# SparkFun-Cherry-MX-Switch-Breakout.net
KiCad netlist of a schematic drawn in EAGLE
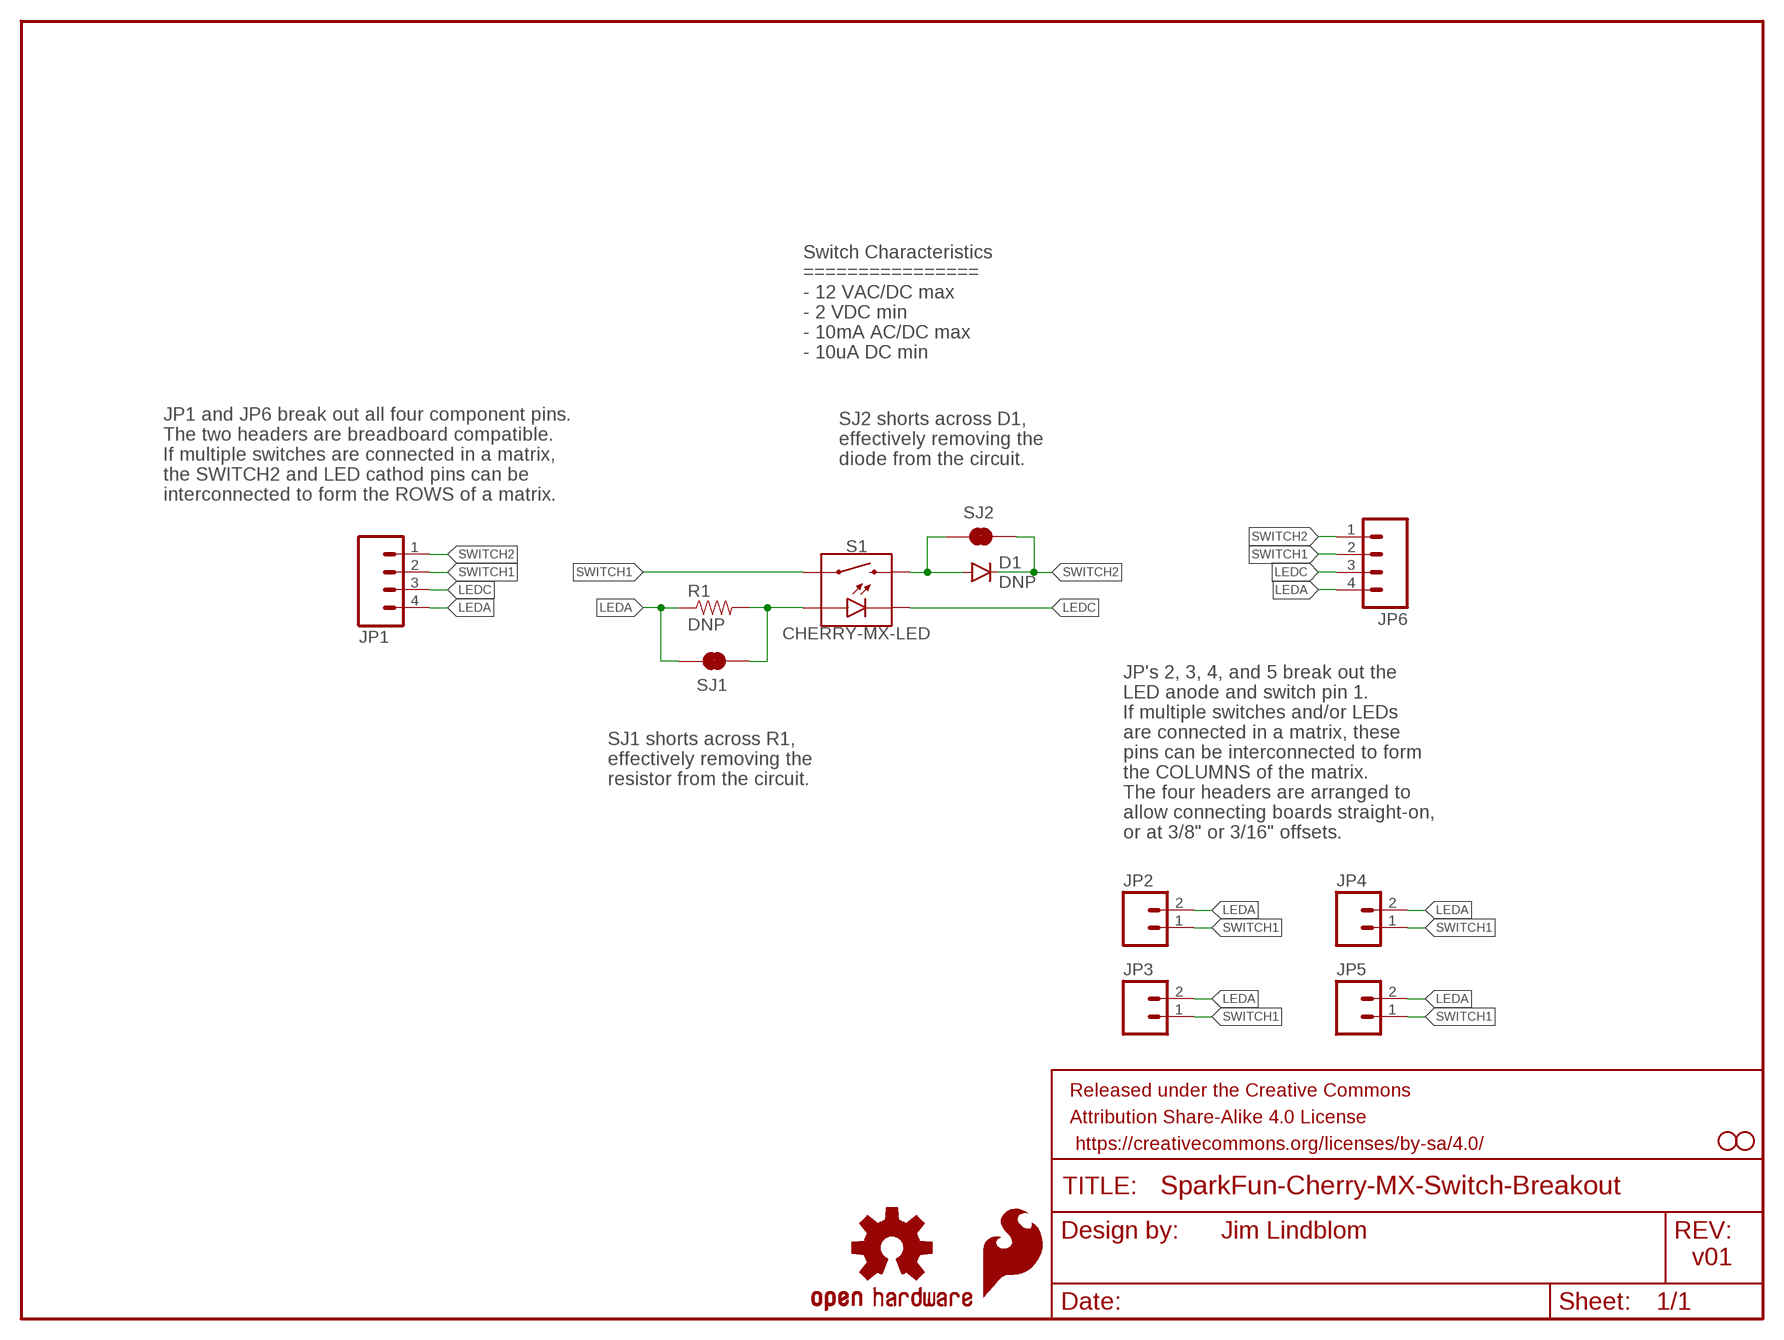
[diagram p0: schematic, sheet 1]

(export (version "E")
  (design (tool "Eeschema 10.0.6"))
  (components
    (comp (ref "D1")
      (value "DNP")
      (footprint "eagle-import:DIODE-PTH-0.1")
      (libsource (lib "eagle-import") (part "DIODEPTH-VERT-0.1"))
    )
    (comp (ref "FRAME1")
      (value "FRAME-LETTER")
      (footprint "eagle-import:CREATIVE_COMMONS")
      (libsource (lib "eagle-import") (part "FRAME-LETTER"))
    )
    (comp (ref "JP1")
      (value "M04NO_SILK_ALL_ROUND")
      (footprint "eagle-import:1X04_NO_SILK_ALL_ROUND")
      (libsource (lib "eagle-import") (part "M04NO_SILK_ALL_ROUND"))
    )
    (comp (ref "JP2")
      (value "M021X02_NO_SILK")
      (footprint "eagle-import:1X02_NO_SILK")
      (libsource (lib "eagle-import") (part "M021X02_NO_SILK"))
    )
    (comp (ref "JP3")
      (value "M021X02_NO_SILK")
      (footprint "eagle-import:1X02_NO_SILK")
      (libsource (lib "eagle-import") (part "M021X02_NO_SILK"))
    )
    (comp (ref "JP4")
      (value "M021X02_NO_SILK")
      (footprint "eagle-import:1X02_NO_SILK")
      (libsource (lib "eagle-import") (part "M021X02_NO_SILK"))
    )
    (comp (ref "JP5")
      (value "M021X02_NO_SILK")
      (footprint "eagle-import:1X02_NO_SILK")
      (libsource (lib "eagle-import") (part "M021X02_NO_SILK"))
    )
    (comp (ref "JP6")
      (value "M04NO_SILK_ALL_ROUND")
      (footprint "eagle-import:1X04_NO_SILK_ALL_ROUND")
      (libsource (lib "eagle-import") (part "M04NO_SILK_ALL_ROUND"))
    )
    (comp (ref "LOGO1")
      (value "OSHW-LOGOS")
      (footprint "eagle-import:OSHW-LOGO-S")
      (libsource (lib "eagle-import") (part "OSHW-LOGOS"))
    )
    (comp (ref "LOGO2")
      (value "SFE_LOGO_FLAME.1_INCH")
      (footprint "eagle-import:SFE_LOGO_FLAME_.1")
      (libsource (lib "eagle-import") (part "SFE_LOGO_FLAME.1_INCH"))
    )
    (comp (ref "R1")
      (value "DNP")
      (footprint "eagle-import:AXIAL-0.1")
      (libsource (lib "eagle-import") (part "RESISTORPTH-1/4W-VERT"))
    )
    (comp (ref "S1")
      (value "CHERRY-MX-LED")
      (footprint "eagle-import:CHERRY-MX-LED")
      (libsource (lib "eagle-import") (part "CHERRY-MX-LED"))
    )
    (comp (ref "SJ1")
      (value "JUMPER-PAD-2-NC_BY_TRACENO_SILK")
      (footprint "eagle-import:PAD-JUMPER-2-NC_BY_TRACE_NO_SILK")
      (libsource (lib "eagle-import") (part "JUMPER-PAD-2-NC_BY_TRACENO_SILK"))
    )
    (comp (ref "SJ2")
      (value "JUMPER-PAD-2-NC_BY_TRACENO_SILK")
      (footprint "eagle-import:PAD-JUMPER-2-NC_BY_TRACE_NO_SILK")
      (libsource (lib "eagle-import") (part "JUMPER-PAD-2-NC_BY_TRACENO_SILK"))
    )
    (comp (ref "STANDOFF1")
      (value "STAND-OFF2-56")
      (footprint "eagle-import:STAND-OFF-2-56")
      (libsource (lib "eagle-import") (part "STAND-OFF2-56"))
    )
    (comp (ref "STANDOFF2")
      (value "STAND-OFF2-56")
      (footprint "eagle-import:STAND-OFF-2-56")
      (libsource (lib "eagle-import") (part "STAND-OFF2-56"))
    )
  )
  (nets
    (net (code "1") (name "LEDA") (class "Default")
      (node (ref "JP1") (pin "4") (pinfunction "4_4") (pintype "passive"))
      (node (ref "JP2") (pin "2") (pinfunction "2_2") (pintype "passive"))
      (node (ref "JP3") (pin "2") (pinfunction "2_2") (pintype "passive"))
      (node (ref "JP4") (pin "2") (pinfunction "2_2") (pintype "passive"))
      (node (ref "JP5") (pin "2") (pinfunction "2_2") (pintype "passive"))
      (node (ref "JP6") (pin "4") (pinfunction "4_4") (pintype "passive"))
      (node (ref "R1") (pin "P$1") (pinfunction "1_P$1") (pintype "passive"))
      (node (ref "SJ1") (pin "1") (pinfunction "1_1") (pintype "passive"))
    )
    (net (code "2") (name "LEDC") (class "Default")
      (node (ref "JP1") (pin "3") (pinfunction "3_3") (pintype "passive"))
      (node (ref "JP6") (pin "3") (pinfunction "3_3") (pintype "passive"))
      (node (ref "S1") (pin "K") (pinfunction "C_K") (pintype "passive"))
    )
    (net (code "3") (name "Net-(D1-PadA)") (class "Default")
      (node (ref "D1") (pin "A") (pinfunction "A_A") (pintype "passive"))
      (node (ref "S1") (pin "S2") (pinfunction "S2_S2") (pintype "passive"))
      (node (ref "SJ2") (pin "1") (pinfunction "1_1") (pintype "passive"))
    )
    (net (code "4") (name "Net-(R1-2)") (class "Default")
      (node (ref "R1") (pin "P$2") (pinfunction "2_P$2") (pintype "passive"))
      (node (ref "S1") (pin "A") (pinfunction "A_A") (pintype "passive"))
      (node (ref "SJ1") (pin "2") (pinfunction "2_2") (pintype "passive"))
    )
    (net (code "5") (name "SWITCH1") (class "Default")
      (node (ref "JP1") (pin "2") (pinfunction "2_2") (pintype "passive"))
      (node (ref "JP2") (pin "1") (pinfunction "1_1") (pintype "passive"))
      (node (ref "JP3") (pin "1") (pinfunction "1_1") (pintype "passive"))
      (node (ref "JP4") (pin "1") (pinfunction "1_1") (pintype "passive"))
      (node (ref "JP5") (pin "1") (pinfunction "1_1") (pintype "passive"))
      (node (ref "JP6") (pin "2") (pinfunction "2_2") (pintype "passive"))
      (node (ref "S1") (pin "S1") (pinfunction "S1_S1") (pintype "passive"))
    )
    (net (code "6") (name "SWITCH2") (class "Default")
      (node (ref "D1") (pin "C") (pinfunction "C_C") (pintype "passive"))
      (node (ref "JP1") (pin "1") (pinfunction "1_1") (pintype "passive"))
      (node (ref "JP6") (pin "1") (pinfunction "1_1") (pintype "passive"))
      (node (ref "SJ2") (pin "2") (pinfunction "2_2") (pintype "passive"))
    )
  )
)
